# urbanturbine.net
KiCad netlist of a schematic drawn in Altium Designer
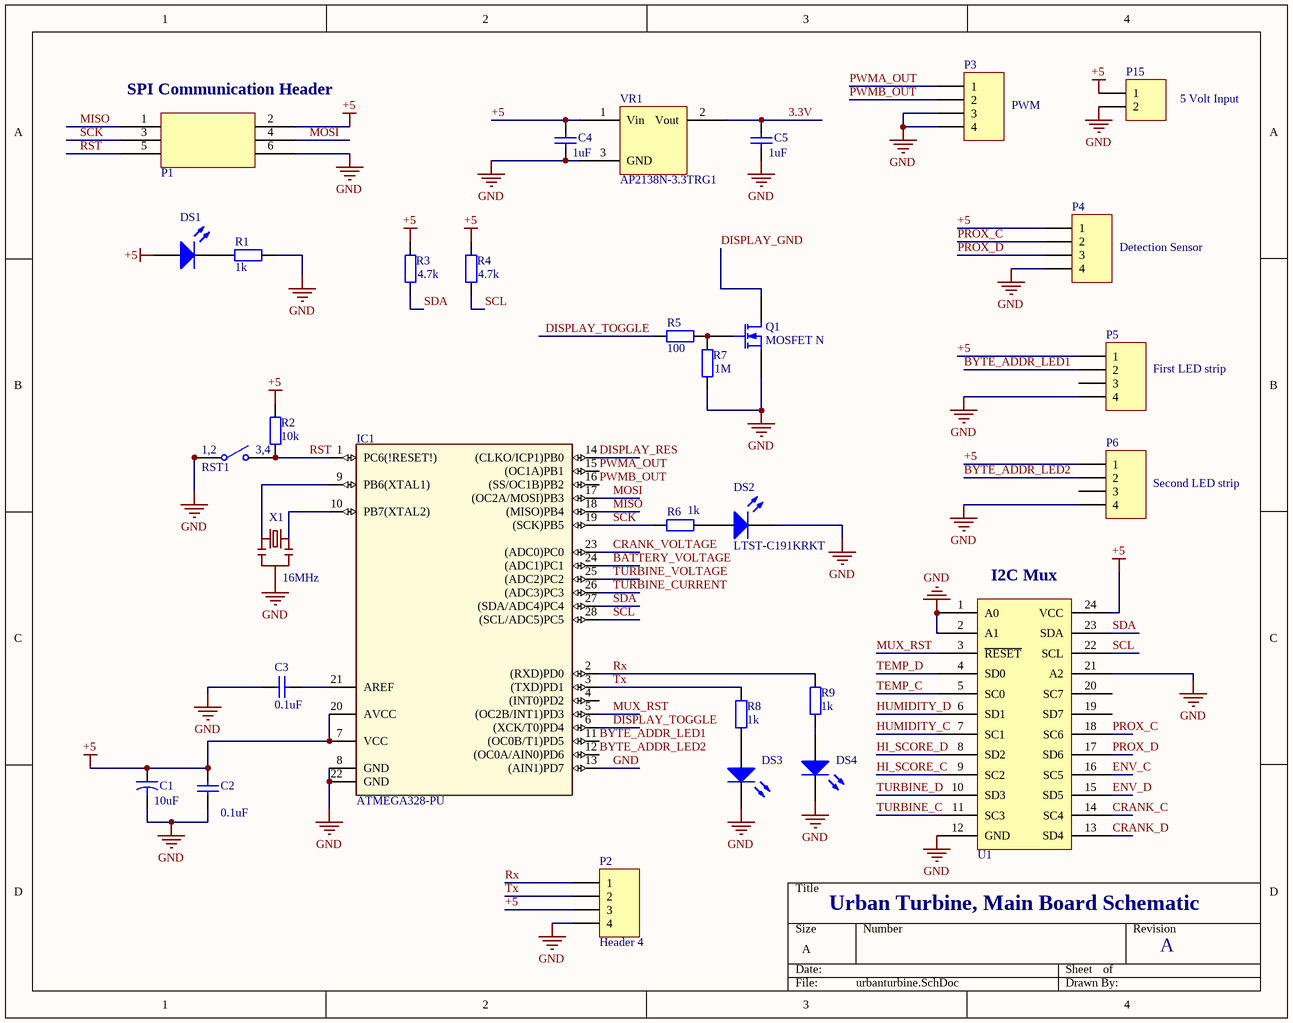
[diagram p0: urbanturbine.SchDoc]

(export (version "E")
  (design (tool "Eeschema 10.0.6"))
  (components
    (comp (ref "C1")
      (value "10uF")
      (footprint "CAPR5-4X5")
      (description "Capacitor")
      (fields (field (name "Comment") "Cap2") (field (name "PUBLISHER") "Altium Limited"))
      (libsource (lib "Miscellaneous Devices") (part "Cap2"))
    )
    (comp (ref "C2")
      (value "0.1uF")
      (footprint "RAD-0.1")
      (description "Capacitor")
      (fields (field (name "PUBLISHER") "Altium Limited"))
      (libsource (lib "Miscellaneous Devices") (part "Cap"))
    )
    (comp (ref "C3")
      (value "0.1uF")
      (footprint "RAD-0.1")
      (description "Capacitor")
      (fields (field (name "Comment") "C1005X7R1H104K050BB") (field (name "PUBLISHER") "Altium Limited"))
      (libsource (lib "Miscellaneous Devices") (part "Cap"))
    )
    (comp (ref "C4")
      (value "1uF")
      (footprint "RAD-0.1")
      (description "Capacitor")
      (fields (field (name "Comment") "Cap") (field (name "PUBLISHER") "Altium Limited"))
      (libsource (lib "Miscellaneous Devices") (part "Cap"))
    )
    (comp (ref "C5")
      (value "1uF")
      (footprint "RAD-0.1")
      (description "Capacitor")
      (fields (field (name "Comment") "Cap") (field (name "PUBLISHER") "Altium Limited"))
      (libsource (lib "Miscellaneous Devices") (part "Cap"))
    )
    (comp (ref "DS1")
      (value "LTST-C191KGKT")
      (footprint "LED-1")
      (description "Typical RED GaAs LED")
      (fields (field (name "PUBLISHER") "Altium Limited"))
      (libsource (lib "Miscellaneous Devices") (part "LED1"))
    )
    (comp (ref "DS2")
      (value "LTST-C191KRKT")
      (footprint "LED-1")
      (description "Typical RED GaAs LED")
      (fields (field (name "PUBLISHER") "Altium Limited"))
      (libsource (lib "Miscellaneous Devices") (part "LED1"))
    )
    (comp (ref "DS3")
      (value "LTST-C191KRKT")
      (footprint "LED-1")
      (description "Typical RED GaAs LED")
      (fields (field (name "PUBLISHER") "Altium Limited"))
      (libsource (lib "Miscellaneous Devices") (part "LED1"))
    )
    (comp (ref "DS4")
      (value "LTST-C191KRKT")
      (footprint "LED-1")
      (description "Typical RED GaAs LED")
      (fields (field (name "PUBLISHER") "Altium Limited"))
      (libsource (lib "Miscellaneous Devices") (part "LED1"))
    )
    (comp (ref "IC1")
      (value "ATMEGA328-PU")
      (footprint "*DIL28")
      (description "IC MCU 8BIT 32KB FLASH 28DIP")
      (fields (field (name "MF") "Microchip Technology"))
      (libsource (lib "altium-import") (part "root_0_ATMEGA328-PU_"))
    )
    (comp (ref "P1")
      (value "M20-9980346")
      (footprint "2X3")
      (description "DIL VERTICAL PC TAIL PIN HEADER")
      (fields (field (name "MANUFACTURER") "Harwin Inc."))
      (libsource (lib "Main SCH Library") (part "M20-9980346"))
    )
    (comp (ref "P2")
      (value "Header 4")
      (footprint "HDR1X4")
      (description "Header, 4-Pin")
      (fields (field (name "PUBLISHER") "Altium Limited"))
      (libsource (lib "Miscellaneous Connectors") (part "Header 4"))
    )
    (comp (ref "P3")
      (value "~")
      (footprint "HDR1X4")
      (description "Header, 4-Pin")
      (fields (field (name "PUBLISHER") "Altium Limited"))
      (libsource (lib "Miscellaneous Connectors") (part "Header 4"))
    )
    (comp (ref "P4")
      (value "~")
      (footprint "HDR1X4")
      (description "Header, 4-Pin")
      (fields (field (name "PUBLISHER") "Altium Limited"))
      (libsource (lib "Miscellaneous Connectors") (part "Header 4"))
    )
    (comp (ref "P5")
      (value "~")
      (footprint "HDR1X4")
      (description "Header, 4-Pin")
      (fields (field (name "PUBLISHER") "Altium Limited"))
      (libsource (lib "Miscellaneous Connectors") (part "Header 4"))
    )
    (comp (ref "P6")
      (value "~")
      (footprint "HDR1X4")
      (description "Header, 4-Pin")
      (fields (field (name "PUBLISHER") "Altium Limited"))
      (libsource (lib "Miscellaneous Connectors") (part "Header 4"))
    )
    (comp (ref "P15")
      (value "~")
      (footprint "HDR1X2")
      (description "Header, 2-Pin")
      (fields (field (name "PUBLISHER") "Altium Limited"))
      (libsource (lib "Miscellaneous Connectors") (part "Header 2"))
    )
    (comp (ref "Q1")
      (value "MOSFET N")
      (footprint "SOT23127P600-8N")
      (description "N-channel MOSFET")
      (libsource (lib "urbanturbine") (part "MOSFET N"))
    )
    (comp (ref "R1")
      (value "1k")
      (footprint "AXIAL-0.4")
      (description "Resistor")
      (fields (field (name "Comment") "RC0603JR-071KL") (field (name "PUBLISHER") "Altium Limited"))
      (libsource (lib "Miscellaneous Devices") (part "Res2"))
    )
    (comp (ref "R2")
      (value "10k")
      (footprint "AXIAL-0.4")
      (description "Resistor")
      (fields (field (name "Comment") "Res1") (field (name "PUBLISHER") "Altium Limited"))
      (libsource (lib "") (part "Res2_1"))
    )
    (comp (ref "R3")
      (value "4.7k")
      (footprint "AXIAL-0.4")
      (description "Resistor")
      (fields (field (name "Comment") "Res2") (field (name "PUBLISHER") "Altium Limited"))
      (libsource (lib "") (part "Res2_2"))
    )
    (comp (ref "R4")
      (value "4.7k")
      (footprint "AXIAL-0.4")
      (description "Resistor")
      (fields (field (name "Comment") "Res2") (field (name "PUBLISHER") "Altium Limited"))
      (libsource (lib "") (part "Res2_2"))
    )
    (comp (ref "R5")
      (value "100")
      (footprint "AXIAL-0.4")
      (description "Resistor")
      (fields (field (name "Comment") "ERJ-3EKF1002V") (field (name "PUBLISHER") "Altium Limited"))
      (libsource (lib "") (part "Res2_3"))
    )
    (comp (ref "R6")
      (value "1k")
      (footprint "AXIAL-0.4")
      (description "Resistor")
      (fields (field (name "Comment") "Res1") (field (name "PUBLISHER") "Altium Limited"))
      (libsource (lib "Miscellaneous Devices") (part "Res2"))
    )
    (comp (ref "R7")
      (value "1M")
      (footprint "AXIAL-0.4")
      (description "Resistor")
      (fields (field (name "Comment") "Res2") (field (name "PUBLISHER") "Altium Limited"))
      (libsource (lib "") (part "Res2_1"))
    )
    (comp (ref "R8")
      (value "1k")
      (footprint "AXIAL-0.4")
      (description "Resistor")
      (fields (field (name "Comment") "Res1") (field (name "PUBLISHER") "Altium Limited"))
      (libsource (lib "") (part "Res2_1"))
    )
    (comp (ref "R9")
      (value "1k")
      (footprint "AXIAL-0.4")
      (description "Resistor")
      (fields (field (name "Comment") "Res1") (field (name "PUBLISHER") "Altium Limited"))
      (libsource (lib "") (part "Res2_1"))
    )
    (comp (ref "RST1")
      (value "PTS645SH50SMTR92 LFS")
      (footprint "TACTILE SWITCH SMD")
      (description "SWITCH TACTILE SPST-NO 0.05A 12V")
      (fields (field (name "MANUFACTURER") "C&K Components"))
      (libsource (lib "Jason_SCH Library") (part "PTS645SH50SMTR92 LFS"))
    )
    (comp (ref "U1")
      (value "TCA9548A")
      (footprint "TCA9548A")
      (description "IIC multiplexor")
      (libsource (lib "urbanturbine") (part "TCA9548A"))
    )
    (comp (ref "VR1")
      (value "AP2138N-3.3TRG1")
      (footprint "SOT23_M")
      (description "IC REG LINEAR 3.3V 250MA SOT23-3")
      (libsource (lib "altium-import") (part "root_0_AP2138N-3.3TRG1_"))
    )
    (comp (ref "X1")
      (value "16MHz")
      (footprint "Jason_PCB Library:RESONATOR-SMD")
      (description "CER RESONATOR 16MHZ SMD")
      (fields
        (field (name "MANUFACTURER") "Murata Electronics North America")
        (field (name "MANUFACTURER PART NUMBER") "CSTCE10M0G55Z-R0")
      )
      (libsource (lib "Jason_SCH Library") (part "CSTNE16M0VH3C000R0"))
    )
  )
  (nets
    (net (code "1") (name "+5") (class "Default")
      (node (ref "C1") (pin "1") (pinfunction "1_1") (pintype "passive"))
      (node (ref "C2") (pin "2") (pinfunction "2_2") (pintype "passive"))
      (node (ref "C4") (pin "2") (pinfunction "2_2") (pintype "passive"))
      (node (ref "DS1") (pin "1") (pinfunction "A_1") (pintype "passive"))
      (node (ref "IC1") (pin "20") (pinfunction "AVCC_20") (pintype "power_in"))
      (node (ref "IC1") (pin "7") (pinfunction "VCC_7") (pintype "power_in"))
      (node (ref "P1") (pin "2") (pintype "passive"))
      (node (ref "P15") (pin "1") (pinfunction "1_1") (pintype "passive"))
      (node (ref "P2") (pin "3") (pinfunction "3_3") (pintype "passive"))
      (node (ref "P4") (pin "1") (pinfunction "1_1") (pintype "passive"))
      (node (ref "P5") (pin "1") (pinfunction "1_1") (pintype "passive"))
      (node (ref "P6") (pin "1") (pinfunction "1_1") (pintype "passive"))
      (node (ref "R2") (pin "1") (pinfunction "1_1") (pintype "passive"))
      (node (ref "R3") (pin "2") (pinfunction "2_2") (pintype "passive"))
      (node (ref "R4") (pin "2") (pinfunction "2_2") (pintype "passive"))
      (node (ref "U1") (pin "24") (pinfunction "VCC_24") (pintype "passive"))
      (node (ref "VR1") (pin "1") (pinfunction "Vin_1") (pintype "passive"))
    )
    (net (code "2") (name "/3.3V") (class "Default")
      (node (ref "C5") (pin "2") (pinfunction "2_2") (pintype "passive"))
      (node (ref "VR1") (pin "2") (pinfunction "Vout_2") (pintype "passive"))
    )
    (net (code "3") (name "/BATTERY_VOLTAGE") (class "Default")
      (node (ref "IC1") (pin "24") (pinfunction "(ADC1)PC1_24") (pintype "bidirectional"))
    )
    (net (code "4") (name "/BYTE_ADDR_LED1") (class "Default")
      (node (ref "IC1") (pin "11") (pinfunction "(OC0B/T1)PD5_11") (pintype "bidirectional"))
      (node (ref "P5") (pin "2") (pinfunction "2_2") (pintype "passive"))
    )
    (net (code "5") (name "/BYTE_ADDR_LED2") (class "Default")
      (node (ref "IC1") (pin "12") (pinfunction "(OC0A/AIN0)PD6_12") (pintype "bidirectional"))
      (node (ref "P6") (pin "2") (pinfunction "2_2") (pintype "passive"))
    )
    (net (code "6") (name "/CRANK_C") (class "Default")
      (node (ref "U1") (pin "14") (pinfunction "SC4_14") (pintype "passive"))
    )
    (net (code "7") (name "/CRANK_D") (class "Default")
      (node (ref "U1") (pin "13") (pinfunction "SD4_13") (pintype "passive"))
    )
    (net (code "8") (name "/CRANK_VOLTAGE") (class "Default")
      (node (ref "IC1") (pin "23") (pinfunction "(ADC0)PC0_23") (pintype "bidirectional"))
    )
    (net (code "9") (name "/DISPLAY_GND") (class "Default")
      (node (ref "Q1") (pin "3") (pinfunction "D_3") (pintype "passive"))
    )
    (net (code "10") (name "/DISPLAY_RES") (class "Default")
      (node (ref "IC1") (pin "14") (pinfunction "(CLKO/ICP1)PB0_14") (pintype "bidirectional"))
    )
    (net (code "11") (name "/DISPLAY_TOGGLE") (class "Default")
      (node (ref "IC1") (pin "6") (pinfunction "(XCK/T0)PD4_6") (pintype "bidirectional"))
      (node (ref "R5") (pin "2") (pinfunction "2_2") (pintype "passive"))
    )
    (net (code "12") (name "/ENV_C") (class "Default")
      (node (ref "U1") (pin "16") (pinfunction "SC5_16") (pintype "passive"))
    )
    (net (code "13") (name "/ENV_D") (class "Default")
      (node (ref "U1") (pin "15") (pinfunction "SD5_15") (pintype "passive"))
    )
    (net (code "14") (name "/HI_SCORE_C") (class "Default")
      (node (ref "U1") (pin "9") (pinfunction "SC2_9") (pintype "passive"))
    )
    (net (code "15") (name "/HI_SCORE_D") (class "Default")
      (node (ref "U1") (pin "8") (pinfunction "SD2_8") (pintype "passive"))
    )
    (net (code "16") (name "/HUMIDITY_C") (class "Default")
      (node (ref "U1") (pin "7") (pinfunction "SC1_7") (pintype "passive"))
    )
    (net (code "17") (name "/HUMIDITY_D") (class "Default")
      (node (ref "U1") (pin "6") (pinfunction "SD1_6") (pintype "passive"))
    )
    (net (code "18") (name "/MISO") (class "Default")
      (node (ref "IC1") (pin "18") (pinfunction "(MISO)PB4_18") (pintype "bidirectional"))
      (node (ref "P1") (pin "1") (pintype "passive"))
    )
    (net (code "19") (name "/MOSI") (class "Default")
      (node (ref "IC1") (pin "17") (pinfunction "(OC2A/MOSI)PB3_17") (pintype "bidirectional"))
      (node (ref "P1") (pin "4") (pintype "passive"))
    )
    (net (code "20") (name "/MUX_RST") (class "Default")
      (node (ref "IC1") (pin "5") (pinfunction "(OC2B/INT1)PD3_5") (pintype "bidirectional"))
      (node (ref "U1") (pin "3") (pinfunction "~{RESET}_3") (pintype "passive"))
    )
    (net (code "21") (name "/PROX_C") (class "Default")
      (node (ref "P4") (pin "2") (pinfunction "2_2") (pintype "passive"))
      (node (ref "U1") (pin "18") (pinfunction "SC6_18") (pintype "passive"))
    )
    (net (code "22") (name "/PROX_D") (class "Default")
      (node (ref "P4") (pin "3") (pinfunction "3_3") (pintype "passive"))
      (node (ref "U1") (pin "17") (pinfunction "SD6_17") (pintype "passive"))
    )
    (net (code "23") (name "/PWMA_OUT") (class "Default")
      (node (ref "IC1") (pin "15") (pinfunction "(OC1A)PB1_15") (pintype "bidirectional"))
      (node (ref "P3") (pin "1") (pinfunction "1_1") (pintype "passive"))
    )
    (net (code "24") (name "/PWMB_OUT") (class "Default")
      (node (ref "IC1") (pin "16") (pinfunction "(SS/OC1B)PB2_16") (pintype "bidirectional"))
      (node (ref "P3") (pin "2") (pinfunction "2_2") (pintype "passive"))
    )
    (net (code "25") (name "/RST") (class "Default")
      (node (ref "IC1") (pin "1") (pinfunction "PC6(!RESET!)_1") (pintype "bidirectional"))
      (node (ref "P1") (pin "5") (pintype "passive"))
      (node (ref "R2") (pin "2") (pinfunction "2_2") (pintype "passive"))
      (node (ref "RST1") (pin "3") (pinfunction "3_3") (pintype "passive"))
      (node (ref "RST1") (pin "4") (pinfunction "4_4") (pintype "passive"))
    )
    (net (code "26") (name "/Rx") (class "Default")
      (node (ref "IC1") (pin "2") (pinfunction "(RXD)PD0_2") (pintype "bidirectional"))
      (node (ref "P2") (pin "1") (pinfunction "1_1") (pintype "passive"))
      (node (ref "R9") (pin "1") (pinfunction "1_1") (pintype "passive"))
    )
    (net (code "27") (name "/SCK") (class "Default")
      (node (ref "IC1") (pin "19") (pinfunction "(SCK)PB5_19") (pintype "bidirectional"))
      (node (ref "P1") (pin "3") (pintype "passive"))
      (node (ref "R6") (pin "1") (pinfunction "1_1") (pintype "passive"))
    )
    (net (code "28") (name "/SCL") (class "Default")
      (node (ref "IC1") (pin "28") (pinfunction "(SCL/ADC5)PC5_28") (pintype "bidirectional"))
      (node (ref "R4") (pin "1") (pinfunction "1_1") (pintype "passive"))
      (node (ref "U1") (pin "22") (pinfunction "SCL_22") (pintype "passive"))
    )
    (net (code "29") (name "/SDA") (class "Default")
      (node (ref "IC1") (pin "27") (pinfunction "(SDA/ADC4)PC4_27") (pintype "bidirectional"))
      (node (ref "R3") (pin "1") (pinfunction "1_1") (pintype "passive"))
      (node (ref "U1") (pin "23") (pinfunction "SDA_23") (pintype "passive"))
    )
    (net (code "30") (name "/TEMP_C") (class "Default")
      (node (ref "U1") (pin "5") (pinfunction "SC0_5") (pintype "passive"))
    )
    (net (code "31") (name "/TEMP_D") (class "Default")
      (node (ref "U1") (pin "4") (pinfunction "SD0_4") (pintype "passive"))
    )
    (net (code "32") (name "/TURBINE_C") (class "Default")
      (node (ref "U1") (pin "11") (pinfunction "SC3_11") (pintype "passive"))
    )
    (net (code "33") (name "/TURBINE_CURRENT") (class "Default")
      (node (ref "IC1") (pin "26") (pinfunction "(ADC3)PC3_26") (pintype "bidirectional"))
    )
    (net (code "34") (name "/TURBINE_D") (class "Default")
      (node (ref "U1") (pin "10") (pinfunction "SD3_10") (pintype "passive"))
    )
    (net (code "35") (name "/TURBINE_VOLTAGE") (class "Default")
      (node (ref "IC1") (pin "25") (pinfunction "(ADC2)PC2_25") (pintype "bidirectional"))
    )
    (net (code "36") (name "/Tx") (class "Default")
      (node (ref "IC1") (pin "3") (pinfunction "(TXD)PD1_3") (pintype "bidirectional"))
      (node (ref "P2") (pin "2") (pinfunction "2_2") (pintype "passive"))
      (node (ref "R8") (pin "1") (pinfunction "1_1") (pintype "passive"))
    )
    (net (code "37") (name "GND") (class "Default")
      (node (ref "C1") (pin "2") (pinfunction "2_2") (pintype "passive"))
      (node (ref "C2") (pin "1") (pinfunction "1_1") (pintype "passive"))
      (node (ref "C3") (pin "2") (pinfunction "2_2") (pintype "passive"))
      (node (ref "C4") (pin "1") (pinfunction "1_1") (pintype "passive"))
      (node (ref "C5") (pin "1") (pinfunction "1_1") (pintype "passive"))
      (node (ref "DS2") (pin "2") (pinfunction "K_2") (pintype "passive"))
      (node (ref "DS3") (pin "2") (pinfunction "K_2") (pintype "passive"))
      (node (ref "DS4") (pin "2") (pinfunction "K_2") (pintype "passive"))
      (node (ref "IC1") (pin "13") (pinfunction "(AIN1)PD7_13") (pintype "bidirectional"))
      (node (ref "IC1") (pin "22") (pinfunction "GND_22") (pintype "power_in"))
      (node (ref "IC1") (pin "8") (pinfunction "GND_8") (pintype "power_in"))
      (node (ref "P1") (pin "6") (pintype "passive"))
      (node (ref "P15") (pin "2") (pinfunction "2_2") (pintype "passive"))
      (node (ref "P2") (pin "4") (pinfunction "4_4") (pintype "passive"))
      (node (ref "P3") (pin "3") (pinfunction "3_3") (pintype "passive"))
      (node (ref "P3") (pin "4") (pinfunction "4_4") (pintype "passive"))
      (node (ref "P4") (pin "4") (pinfunction "4_4") (pintype "passive"))
      (node (ref "P5") (pin "4") (pinfunction "4_4") (pintype "passive"))
      (node (ref "P6") (pin "4") (pinfunction "4_4") (pintype "passive"))
      (node (ref "Q1") (pin "2") (pinfunction "S_2") (pintype "passive"))
      (node (ref "R1") (pin "2") (pinfunction "2_2") (pintype "passive"))
      (node (ref "R7") (pin "2") (pinfunction "2_2") (pintype "passive"))
      (node (ref "RST1") (pin "1") (pinfunction "1_1") (pintype "passive"))
      (node (ref "RST1") (pin "2") (pinfunction "2_2") (pintype "passive"))
      (node (ref "U1") (pin "1") (pinfunction "A0_1") (pintype "passive"))
      (node (ref "U1") (pin "12") (pinfunction "GND_12") (pintype "passive"))
      (node (ref "U1") (pin "2") (pinfunction "A1_2") (pintype "passive"))
      (node (ref "U1") (pin "21") (pinfunction "A2_21") (pintype "passive"))
      (node (ref "VR1") (pin "3") (pinfunction "GND_3") (pintype "passive"))
      (node (ref "X1") (pin "2") (pinfunction "2_2") (pintype "passive"))
    )
    (net (code "38") (name "Net-(DS1-K)") (class "Default")
      (node (ref "DS1") (pin "2") (pinfunction "K_2") (pintype "passive"))
      (node (ref "R1") (pin "1") (pinfunction "1_1") (pintype "passive"))
    )
    (net (code "39") (name "Net-(DS2-A)") (class "Default")
      (node (ref "DS2") (pin "1") (pinfunction "A_1") (pintype "passive"))
      (node (ref "R6") (pin "2") (pinfunction "2_2") (pintype "passive"))
    )
    (net (code "40") (name "Net-(DS3-A)") (class "Default")
      (node (ref "DS3") (pin "1") (pinfunction "A_1") (pintype "passive"))
      (node (ref "R8") (pin "2") (pinfunction "2_2") (pintype "passive"))
    )
    (net (code "41") (name "Net-(DS4-A)") (class "Default")
      (node (ref "DS4") (pin "1") (pinfunction "A_1") (pintype "passive"))
      (node (ref "R9") (pin "2") (pinfunction "2_2") (pintype "passive"))
    )
    (net (code "42") (name "Net-(IC1-AREF)") (class "Default")
      (node (ref "C3") (pin "1") (pinfunction "1_1") (pintype "passive"))
      (node (ref "IC1") (pin "21") (pinfunction "AREF_21") (pintype "passive"))
    )
    (net (code "43") (name "Net-(IC1-PB6(XTAL1))") (class "Default")
      (node (ref "IC1") (pin "9") (pinfunction "PB6(XTAL1)_9") (pintype "bidirectional"))
      (node (ref "X1") (pin "3") (pinfunction "3_3") (pintype "passive"))
    )
    (net (code "44") (name "Net-(IC1-PB7(XTAL2))") (class "Default")
      (node (ref "IC1") (pin "10") (pinfunction "PB7(XTAL2)_10") (pintype "bidirectional"))
      (node (ref "X1") (pin "1") (pinfunction "1_1") (pintype "passive"))
    )
    (net (code "45") (name "Net-(Q1-G)") (class "Default")
      (node (ref "Q1") (pin "1") (pinfunction "G_1") (pintype "passive"))
      (node (ref "R5") (pin "1") (pinfunction "1_1") (pintype "passive"))
      (node (ref "R7") (pin "1") (pinfunction "1_1") (pintype "passive"))
    )
    (net (code "46") (name "unconnected-(IC1-(INT0)PD2-Pad4)") (class "Default")
      (node (ref "IC1") (pin "4") (pinfunction "(INT0)PD2_4") (pintype "bidirectional"))
    )
    (net (code "47") (name "unconnected-(P5-Pad3)") (class "Default")
      (node (ref "P5") (pin "3") (pinfunction "3_3") (pintype "passive"))
    )
    (net (code "48") (name "unconnected-(P6-Pad3)") (class "Default")
      (node (ref "P6") (pin "3") (pinfunction "3_3") (pintype "passive"))
    )
    (net (code "49") (name "unconnected-(U1-SC7-Pad20)") (class "Default")
      (node (ref "U1") (pin "20") (pinfunction "SC7_20") (pintype "passive"))
    )
    (net (code "50") (name "unconnected-(U1-SD7-Pad19)") (class "Default")
      (node (ref "U1") (pin "19") (pinfunction "SD7_19") (pintype "passive"))
    )
  )
)
